# SensorBoard.net
KiCad netlist of a schematic drawn in EAGLE
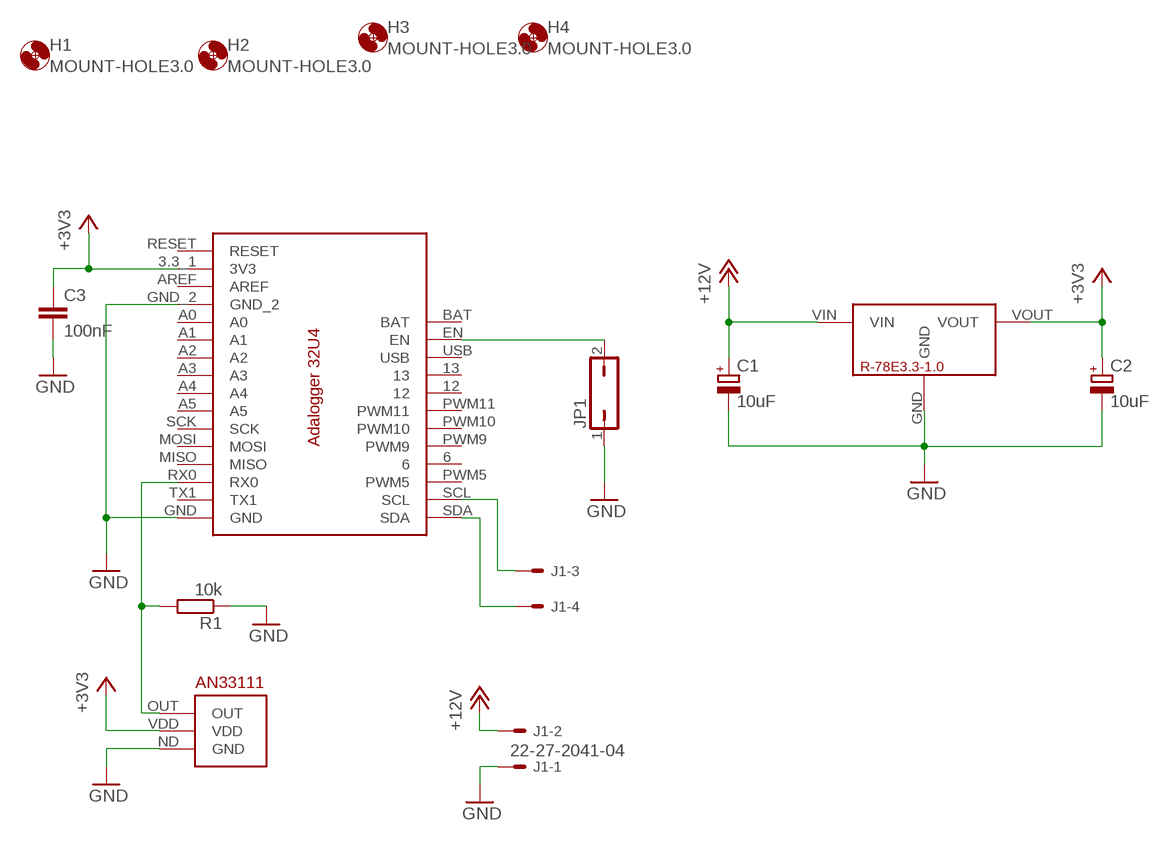
[diagram p0: schematic, sheet 1]

(export (version "E")
  (design (tool "Eeschema 10.0.6"))
  (components
    (comp (ref "C1")
      (value "10uF")
      (footprint "eagle-import:E2,5-7")
      (libsource (lib "eagle-import") (part "CPOL-EUE2.5-7"))
    )
    (comp (ref "C2")
      (value "10uF")
      (footprint "eagle-import:E2,5-7")
      (libsource (lib "eagle-import") (part "CPOL-EUE2.5-7"))
    )
    (comp (ref "C3")
      (value "100nF")
      (footprint "eagle-import:C050-025X075")
      (libsource (lib "eagle-import") (part "C-EU050-025X075"))
    )
    (comp (ref "H1")
      (value "MOUNT-HOLE3.0")
      (footprint "eagle-import:3,0")
      (libsource (lib "eagle-import") (part "MOUNT-HOLE3.0"))
    )
    (comp (ref "H2")
      (value "MOUNT-HOLE3.0")
      (footprint "eagle-import:3,0")
      (libsource (lib "eagle-import") (part "MOUNT-HOLE3.0"))
    )
    (comp (ref "H3")
      (value "MOUNT-HOLE3.0")
      (footprint "eagle-import:3,0")
      (libsource (lib "eagle-import") (part "MOUNT-HOLE3.0"))
    )
    (comp (ref "H4")
      (value "MOUNT-HOLE3.0")
      (footprint "eagle-import:3,0")
      (libsource (lib "eagle-import") (part "MOUNT-HOLE3.0"))
    )
    (comp (ref "J1")
      (value "22-27-2041-04")
      (footprint "eagle-import:6410-04")
      (libsource (lib "eagle-import") (part "22-?-0427-2041"))
    )
    (comp (ref "JP1")
      (value "JP1Q")
      (footprint "eagle-import:JP1")
      (libsource (lib "eagle-import") (part "JP1Q"))
    )
    (comp (ref "R1")
      (value "10k")
      (footprint "eagle-import:0207_7")
      (libsource (lib "eagle-import") (part "R-EU_0207/7"))
    )
    (comp (ref "U$1")
      (value "ADALOGGER_32U4_BOARD")
      (footprint "eagle-import:ADALOGGER_32U4_BOARD")
      (libsource (lib "eagle-import") (part "ADALOGGER_32U4_BOARD"))
    )
    (comp (ref "U$2")
      (value "AMN33111")
      (footprint "eagle-import:AN33111")
      (libsource (lib "eagle-import") (part "AMN33111"))
    )
    (comp (ref "U$3")
      (value "R-78E3.3-1.0")
      (footprint "eagle-import:R-78E3.3-1.0")
      (libsource (lib "eagle-import") (part "R-78E3.3-1.0"))
    )
  )
  (nets
    (net (code "1") (name "+3V3") (class "Default")
      (node (ref "C2") (pin "+") (pinfunction "+_+") (pintype "passive"))
      (node (ref "C3") (pin "1") (pinfunction "1_1") (pintype "passive"))
      (node (ref "U$1") (pin "3.3_1") (pinfunction "3V3_3.3_1") (pintype "bidirectional"))
      (node (ref "U$2") (pin "VDD") (pinfunction "VDD_VDD") (pintype "bidirectional"))
      (node (ref "U$3") (pin "VOUT") (pinfunction "VOUT_VOUT") (pintype "bidirectional"))
    )
    (net (code "2") (name "+12V") (class "Default")
      (node (ref "C1") (pin "+") (pinfunction "+_+") (pintype "passive"))
      (node (ref "J1") (pin "2") (pinfunction "S_2") (pintype "passive"))
      (node (ref "U$3") (pin "VIN") (pinfunction "VIN_VIN") (pintype "bidirectional"))
    )
    (net (code "3") (name "GND") (class "Default")
      (node (ref "C1") (pin "-") (pinfunction "-_-") (pintype "passive"))
      (node (ref "C2") (pin "-") (pinfunction "-_-") (pintype "passive"))
      (node (ref "C3") (pin "2") (pinfunction "2_2") (pintype "passive"))
      (node (ref "J1") (pin "1") (pinfunction "S_1") (pintype "passive"))
      (node (ref "JP1") (pin "1") (pinfunction "1_1") (pintype "passive"))
      (node (ref "R1") (pin "1") (pinfunction "1_1") (pintype "passive"))
      (node (ref "U$1") (pin "GND") (pinfunction "GND_GND") (pintype "bidirectional"))
      (node (ref "U$1") (pin "GND_2") (pinfunction "GND_2_GND_2") (pintype "bidirectional"))
      (node (ref "U$2") (pin "ND") (pinfunction "GND_ND") (pintype "bidirectional"))
      (node (ref "U$3") (pin "GND") (pinfunction "GND_GND") (pintype "bidirectional"))
    )
    (net (code "4") (name "Net-(J1C-S)") (class "Default")
      (node (ref "J1") (pin "3") (pinfunction "S_3") (pintype "passive"))
      (node (ref "U$1") (pin "SCL") (pinfunction "SCL_SCL") (pintype "bidirectional"))
    )
    (net (code "5") (name "Net-(J1D-S)") (class "Default")
      (node (ref "J1") (pin "4") (pinfunction "S_4") (pintype "passive"))
      (node (ref "U$1") (pin "SDA") (pinfunction "SDA_SDA") (pintype "bidirectional"))
    )
    (net (code "6") (name "Net-(JP1-Pad2)") (class "Default")
      (node (ref "JP1") (pin "2") (pinfunction "2_2") (pintype "passive"))
      (node (ref "U$1") (pin "EN") (pinfunction "EN_EN") (pintype "bidirectional"))
    )
    (net (code "7") (name "Net-(R1-Pad2)") (class "Default")
      (node (ref "R1") (pin "2") (pinfunction "2_2") (pintype "passive"))
      (node (ref "U$1") (pin "RX0") (pinfunction "RX0_RX0") (pintype "bidirectional"))
      (node (ref "U$2") (pin "OUT") (pinfunction "OUT_OUT") (pintype "bidirectional"))
    )
    (net (code "8") (name "unconnected-(U$1-Pad6)") (class "Default")
      (node (ref "U$1") (pin "6") (pinfunction "6_6") (pintype "bidirectional"))
    )
    (net (code "9") (name "unconnected-(U$1-Pad12)") (class "Default")
      (node (ref "U$1") (pin "12") (pinfunction "12_12") (pintype "bidirectional"))
    )
    (net (code "10") (name "unconnected-(U$1-Pad13)") (class "Default")
      (node (ref "U$1") (pin "13") (pinfunction "13_13") (pintype "bidirectional"))
    )
    (net (code "11") (name "unconnected-(U$1-PadA0)") (class "Default")
      (node (ref "U$1") (pin "A0") (pinfunction "A0_A0") (pintype "bidirectional"))
    )
    (net (code "12") (name "unconnected-(U$1-PadA1)") (class "Default")
      (node (ref "U$1") (pin "A1") (pinfunction "A1_A1") (pintype "bidirectional"))
    )
    (net (code "13") (name "unconnected-(U$1-PadA2)") (class "Default")
      (node (ref "U$1") (pin "A2") (pinfunction "A2_A2") (pintype "bidirectional"))
    )
    (net (code "14") (name "unconnected-(U$1-PadA3)") (class "Default")
      (node (ref "U$1") (pin "A3") (pinfunction "A3_A3") (pintype "bidirectional"))
    )
    (net (code "15") (name "unconnected-(U$1-PadA4)") (class "Default")
      (node (ref "U$1") (pin "A4") (pinfunction "A4_A4") (pintype "bidirectional"))
    )
    (net (code "16") (name "unconnected-(U$1-PadA5)") (class "Default")
      (node (ref "U$1") (pin "A5") (pinfunction "A5_A5") (pintype "bidirectional"))
    )
    (net (code "17") (name "unconnected-(U$1-PadAREF)") (class "Default")
      (node (ref "U$1") (pin "AREF") (pinfunction "AREF_AREF") (pintype "bidirectional"))
    )
    (net (code "18") (name "unconnected-(U$1-PadBAT)") (class "Default")
      (node (ref "U$1") (pin "BAT") (pinfunction "BAT_BAT") (pintype "bidirectional"))
    )
    (net (code "19") (name "unconnected-(U$1-PadMISO)") (class "Default")
      (node (ref "U$1") (pin "MISO") (pinfunction "MISO_MISO") (pintype "bidirectional"))
    )
    (net (code "20") (name "unconnected-(U$1-PadMOSI)") (class "Default")
      (node (ref "U$1") (pin "MOSI") (pinfunction "MOSI_MOSI") (pintype "bidirectional"))
    )
    (net (code "21") (name "unconnected-(U$1-PadPWM5)") (class "Default")
      (node (ref "U$1") (pin "PWM5") (pinfunction "PWM5_PWM5") (pintype "bidirectional"))
    )
    (net (code "22") (name "unconnected-(U$1-PadPWM9)") (class "Default")
      (node (ref "U$1") (pin "PWM9") (pinfunction "PWM9_PWM9") (pintype "bidirectional"))
    )
    (net (code "23") (name "unconnected-(U$1-PadPWM10)") (class "Default")
      (node (ref "U$1") (pin "PWM10") (pinfunction "PWM10_PWM10") (pintype "bidirectional"))
    )
    (net (code "24") (name "unconnected-(U$1-PadPWM11)") (class "Default")
      (node (ref "U$1") (pin "PWM11") (pinfunction "PWM11_PWM11") (pintype "bidirectional"))
    )
    (net (code "25") (name "unconnected-(U$1-PadRESET)") (class "Default")
      (node (ref "U$1") (pin "RESET") (pinfunction "RESET_RESET") (pintype "bidirectional"))
    )
    (net (code "26") (name "unconnected-(U$1-PadSCK)") (class "Default")
      (node (ref "U$1") (pin "SCK") (pinfunction "SCK_SCK") (pintype "bidirectional"))
    )
    (net (code "27") (name "unconnected-(U$1-PadTX1)") (class "Default")
      (node (ref "U$1") (pin "TX1") (pinfunction "TX1_TX1") (pintype "bidirectional"))
    )
    (net (code "28") (name "unconnected-(U$1-PadUSB)") (class "Default")
      (node (ref "U$1") (pin "USB") (pinfunction "USB_USB") (pintype "bidirectional"))
    )
  )
)
